# grubClub_v3.net
KiCad netlist of a schematic drawn in EAGLE
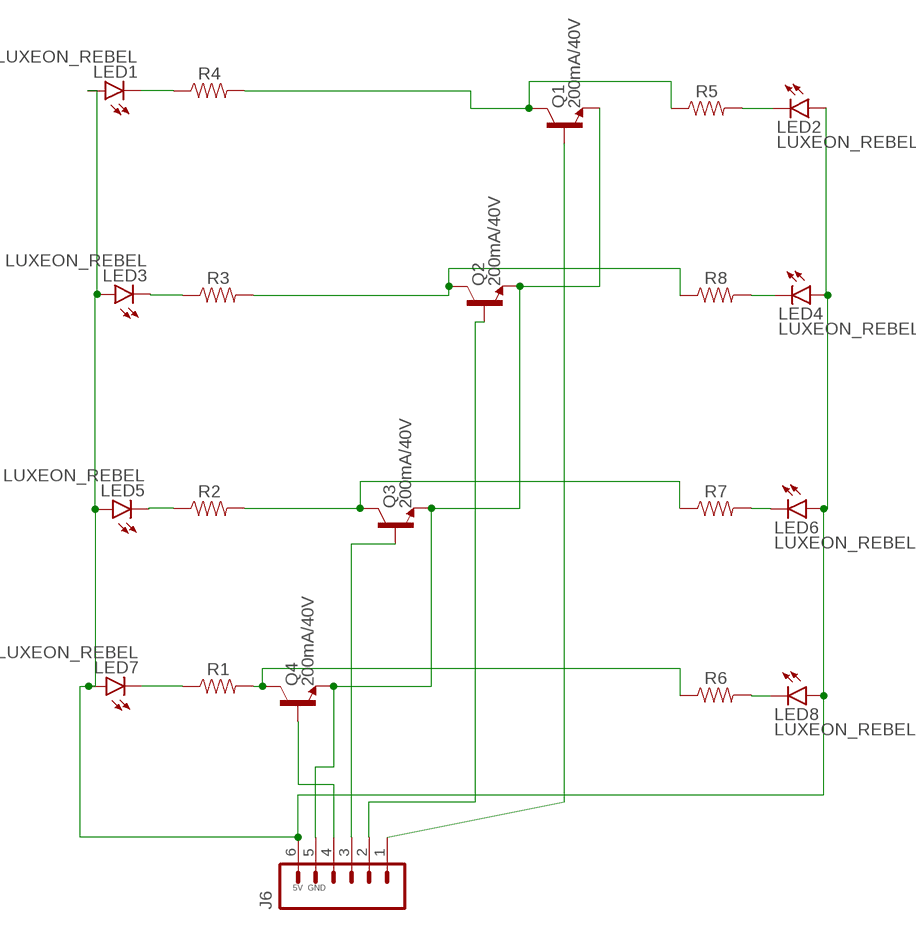
[diagram p0: schematic, sheet 1]

(export (version "E")
  (design (tool "Eeschema 10.0.6"))
  (components
    (comp (ref "J6")
      (value "CONN_06SILK_FEMALE_PTH")
      (footprint "eagle-import:1X06")
      (libsource (lib "eagle-import") (part "CONN_06SILK_FEMALE_PTH"))
    )
    (comp (ref "LED1")
      (value "LUXEON_REBEL")
      (footprint "eagle-import:LUXEON_REBEL")
      (libsource (lib "eagle-import") (part "LUXEON_REBEL"))
    )
    (comp (ref "LED2")
      (value "LUXEON_REBEL")
      (footprint "eagle-import:LUXEON_REBEL")
      (libsource (lib "eagle-import") (part "LUXEON_REBEL"))
    )
    (comp (ref "LED3")
      (value "LUXEON_REBEL")
      (footprint "eagle-import:LUXEON_REBEL")
      (libsource (lib "eagle-import") (part "LUXEON_REBEL"))
    )
    (comp (ref "LED4")
      (value "LUXEON_REBEL")
      (footprint "eagle-import:LUXEON_REBEL")
      (libsource (lib "eagle-import") (part "LUXEON_REBEL"))
    )
    (comp (ref "LED5")
      (value "LUXEON_REBEL")
      (footprint "eagle-import:LUXEON_REBEL")
      (libsource (lib "eagle-import") (part "LUXEON_REBEL"))
    )
    (comp (ref "LED6")
      (value "LUXEON_REBEL")
      (footprint "eagle-import:LUXEON_REBEL")
      (libsource (lib "eagle-import") (part "LUXEON_REBEL"))
    )
    (comp (ref "LED7")
      (value "LUXEON_REBEL")
      (footprint "eagle-import:LUXEON_REBEL")
      (libsource (lib "eagle-import") (part "LUXEON_REBEL"))
    )
    (comp (ref "LED8")
      (value "LUXEON_REBEL")
      (footprint "eagle-import:LUXEON_REBEL")
      (libsource (lib "eagle-import") (part "LUXEON_REBEL"))
    )
    (comp (ref "Q1")
      (value "200mA/40V")
      (footprint "eagle-import:TO-92")
      (libsource (lib "eagle-import") (part "TRANS_NPN-2N3904"))
    )
    (comp (ref "Q2")
      (value "200mA/40V")
      (footprint "eagle-import:TO-92")
      (libsource (lib "eagle-import") (part "TRANS_NPN-2N3904"))
    )
    (comp (ref "Q3")
      (value "200mA/40V")
      (footprint "eagle-import:TO-92")
      (libsource (lib "eagle-import") (part "TRANS_NPN-2N3904"))
    )
    (comp (ref "Q4")
      (value "200mA/40V")
      (footprint "eagle-import:TO-92")
      (libsource (lib "eagle-import") (part "TRANS_NPN-2N3904"))
    )
    (comp (ref "R1")
      (value "RESISTORAXIAL-0.3")
      (footprint "eagle-import:AXIAL-0.3")
      (libsource (lib "eagle-import") (part "RESISTORAXIAL-0.3"))
    )
    (comp (ref "R2")
      (value "RESISTORAXIAL-0.3")
      (footprint "eagle-import:AXIAL-0.3")
      (libsource (lib "eagle-import") (part "RESISTORAXIAL-0.3"))
    )
    (comp (ref "R3")
      (value "RESISTORAXIAL-0.3")
      (footprint "eagle-import:AXIAL-0.3")
      (libsource (lib "eagle-import") (part "RESISTORAXIAL-0.3"))
    )
    (comp (ref "R4")
      (value "RESISTORAXIAL-0.3")
      (footprint "eagle-import:AXIAL-0.3")
      (libsource (lib "eagle-import") (part "RESISTORAXIAL-0.3"))
    )
    (comp (ref "R5")
      (value "RESISTORAXIAL-0.3")
      (footprint "eagle-import:AXIAL-0.3")
      (libsource (lib "eagle-import") (part "RESISTORAXIAL-0.3"))
    )
    (comp (ref "R6")
      (value "RESISTORAXIAL-0.3")
      (footprint "eagle-import:AXIAL-0.3")
      (libsource (lib "eagle-import") (part "RESISTORAXIAL-0.3"))
    )
    (comp (ref "R7")
      (value "RESISTORAXIAL-0.3")
      (footprint "eagle-import:AXIAL-0.3")
      (libsource (lib "eagle-import") (part "RESISTORAXIAL-0.3"))
    )
    (comp (ref "R8")
      (value "RESISTORAXIAL-0.3")
      (footprint "eagle-import:AXIAL-0.3")
      (libsource (lib "eagle-import") (part "RESISTORAXIAL-0.3"))
    )
  )
  (nets
    (net (code "1") (name "Net-(J6-Pad6)") (class "Default")
      (node (ref "J6") (pin "6") (pinfunction "6_6") (pintype "passive"))
      (node (ref "LED1") (pin "A") (pinfunction "A_A") (pintype "passive"))
      (node (ref "LED1") (pin "A@1") (pinfunction "A_A@1") (pintype "passive"))
      (node (ref "LED2") (pin "A") (pinfunction "A_A") (pintype "passive"))
      (node (ref "LED2") (pin "A@1") (pinfunction "A_A@1") (pintype "passive"))
      (node (ref "LED3") (pin "A") (pinfunction "A_A") (pintype "passive"))
      (node (ref "LED3") (pin "A@1") (pinfunction "A_A@1") (pintype "passive"))
      (node (ref "LED4") (pin "A") (pinfunction "A_A") (pintype "passive"))
      (node (ref "LED4") (pin "A@1") (pinfunction "A_A@1") (pintype "passive"))
      (node (ref "LED5") (pin "A") (pinfunction "A_A") (pintype "passive"))
      (node (ref "LED5") (pin "A@1") (pinfunction "A_A@1") (pintype "passive"))
      (node (ref "LED6") (pin "A") (pinfunction "A_A") (pintype "passive"))
      (node (ref "LED6") (pin "A@1") (pinfunction "A_A@1") (pintype "passive"))
      (node (ref "LED7") (pin "A") (pinfunction "A_A") (pintype "passive"))
      (node (ref "LED7") (pin "A@1") (pinfunction "A_A@1") (pintype "passive"))
      (node (ref "LED8") (pin "A") (pinfunction "A_A") (pintype "passive"))
      (node (ref "LED8") (pin "A@1") (pinfunction "A_A@1") (pintype "passive"))
    )
    (net (code "2") (name "Net-(Q1-B)") (class "Default")
      (node (ref "J6") (pin "1") (pinfunction "1_1") (pintype "passive"))
      (node (ref "Q1") (pin "2") (pinfunction "B_2") (pintype "passive"))
    )
    (net (code "3") (name "Net-(Q1-C)") (class "Default")
      (node (ref "Q1") (pin "3") (pinfunction "C_3") (pintype "passive"))
      (node (ref "R4") (pin "P$2") (pinfunction "2_P$2") (pintype "passive"))
      (node (ref "R5") (pin "P$1") (pinfunction "1_P$1") (pintype "passive"))
    )
    (net (code "4") (name "Net-(Q1-E)") (class "Default")
      (node (ref "J6") (pin "5") (pinfunction "5_5") (pintype "passive"))
      (node (ref "Q1") (pin "1") (pinfunction "E_1") (pintype "passive"))
      (node (ref "Q2") (pin "1") (pinfunction "E_1") (pintype "passive"))
      (node (ref "Q3") (pin "1") (pinfunction "E_1") (pintype "passive"))
      (node (ref "Q4") (pin "1") (pinfunction "E_1") (pintype "passive"))
    )
    (net (code "5") (name "Net-(Q2-B)") (class "Default")
      (node (ref "J6") (pin "2") (pinfunction "2_2") (pintype "passive"))
      (node (ref "Q2") (pin "2") (pinfunction "B_2") (pintype "passive"))
    )
    (net (code "6") (name "Net-(Q2-C)") (class "Default")
      (node (ref "Q2") (pin "3") (pinfunction "C_3") (pintype "passive"))
      (node (ref "R3") (pin "P$2") (pinfunction "2_P$2") (pintype "passive"))
      (node (ref "R8") (pin "P$1") (pinfunction "1_P$1") (pintype "passive"))
    )
    (net (code "7") (name "Net-(Q3-B)") (class "Default")
      (node (ref "J6") (pin "3") (pinfunction "3_3") (pintype "passive"))
      (node (ref "Q3") (pin "2") (pinfunction "B_2") (pintype "passive"))
    )
    (net (code "8") (name "Net-(Q3-C)") (class "Default")
      (node (ref "Q3") (pin "3") (pinfunction "C_3") (pintype "passive"))
      (node (ref "R2") (pin "P$2") (pinfunction "2_P$2") (pintype "passive"))
      (node (ref "R7") (pin "P$1") (pinfunction "1_P$1") (pintype "passive"))
    )
    (net (code "9") (name "Net-(Q4-B)") (class "Default")
      (node (ref "J6") (pin "4") (pinfunction "4_4") (pintype "passive"))
      (node (ref "Q4") (pin "2") (pinfunction "B_2") (pintype "passive"))
    )
    (net (code "10") (name "Net-(Q4-C)") (class "Default")
      (node (ref "Q4") (pin "3") (pinfunction "C_3") (pintype "passive"))
      (node (ref "R1") (pin "P$2") (pinfunction "2_P$2") (pintype "passive"))
      (node (ref "R6") (pin "P$1") (pinfunction "1_P$1") (pintype "passive"))
    )
    (net (code "11") (name "Net-(R1-1)") (class "Default")
      (node (ref "LED7") (pin "C") (pinfunction "C_C") (pintype "passive"))
      (node (ref "LED7") (pin "C@1") (pinfunction "C_C@1") (pintype "passive"))
      (node (ref "R1") (pin "P$1") (pinfunction "1_P$1") (pintype "passive"))
    )
    (net (code "12") (name "Net-(R2-1)") (class "Default")
      (node (ref "LED5") (pin "C") (pinfunction "C_C") (pintype "passive"))
      (node (ref "LED5") (pin "C@1") (pinfunction "C_C@1") (pintype "passive"))
      (node (ref "R2") (pin "P$1") (pinfunction "1_P$1") (pintype "passive"))
    )
    (net (code "13") (name "Net-(R3-1)") (class "Default")
      (node (ref "LED3") (pin "C") (pinfunction "C_C") (pintype "passive"))
      (node (ref "LED3") (pin "C@1") (pinfunction "C_C@1") (pintype "passive"))
      (node (ref "R3") (pin "P$1") (pinfunction "1_P$1") (pintype "passive"))
    )
    (net (code "14") (name "Net-(R4-1)") (class "Default")
      (node (ref "LED1") (pin "C") (pinfunction "C_C") (pintype "passive"))
      (node (ref "LED1") (pin "C@1") (pinfunction "C_C@1") (pintype "passive"))
      (node (ref "R4") (pin "P$1") (pinfunction "1_P$1") (pintype "passive"))
    )
    (net (code "15") (name "Net-(R5-2)") (class "Default")
      (node (ref "LED2") (pin "C") (pinfunction "C_C") (pintype "passive"))
      (node (ref "LED2") (pin "C@1") (pinfunction "C_C@1") (pintype "passive"))
      (node (ref "R5") (pin "P$2") (pinfunction "2_P$2") (pintype "passive"))
    )
    (net (code "16") (name "Net-(R6-2)") (class "Default")
      (node (ref "LED8") (pin "C") (pinfunction "C_C") (pintype "passive"))
      (node (ref "LED8") (pin "C@1") (pinfunction "C_C@1") (pintype "passive"))
      (node (ref "R6") (pin "P$2") (pinfunction "2_P$2") (pintype "passive"))
    )
    (net (code "17") (name "Net-(R7-2)") (class "Default")
      (node (ref "LED6") (pin "C") (pinfunction "C_C") (pintype "passive"))
      (node (ref "LED6") (pin "C@1") (pinfunction "C_C@1") (pintype "passive"))
      (node (ref "R7") (pin "P$2") (pinfunction "2_P$2") (pintype "passive"))
    )
    (net (code "18") (name "Net-(R8-2)") (class "Default")
      (node (ref "LED4") (pin "C") (pinfunction "C_C") (pintype "passive"))
      (node (ref "LED4") (pin "C@1") (pinfunction "C_C@1") (pintype "passive"))
      (node (ref "R8") (pin "P$2") (pinfunction "2_P$2") (pintype "passive"))
    )
  )
)
